# Alarm.net
KiCad netlist of a schematic drawn in EAGLE
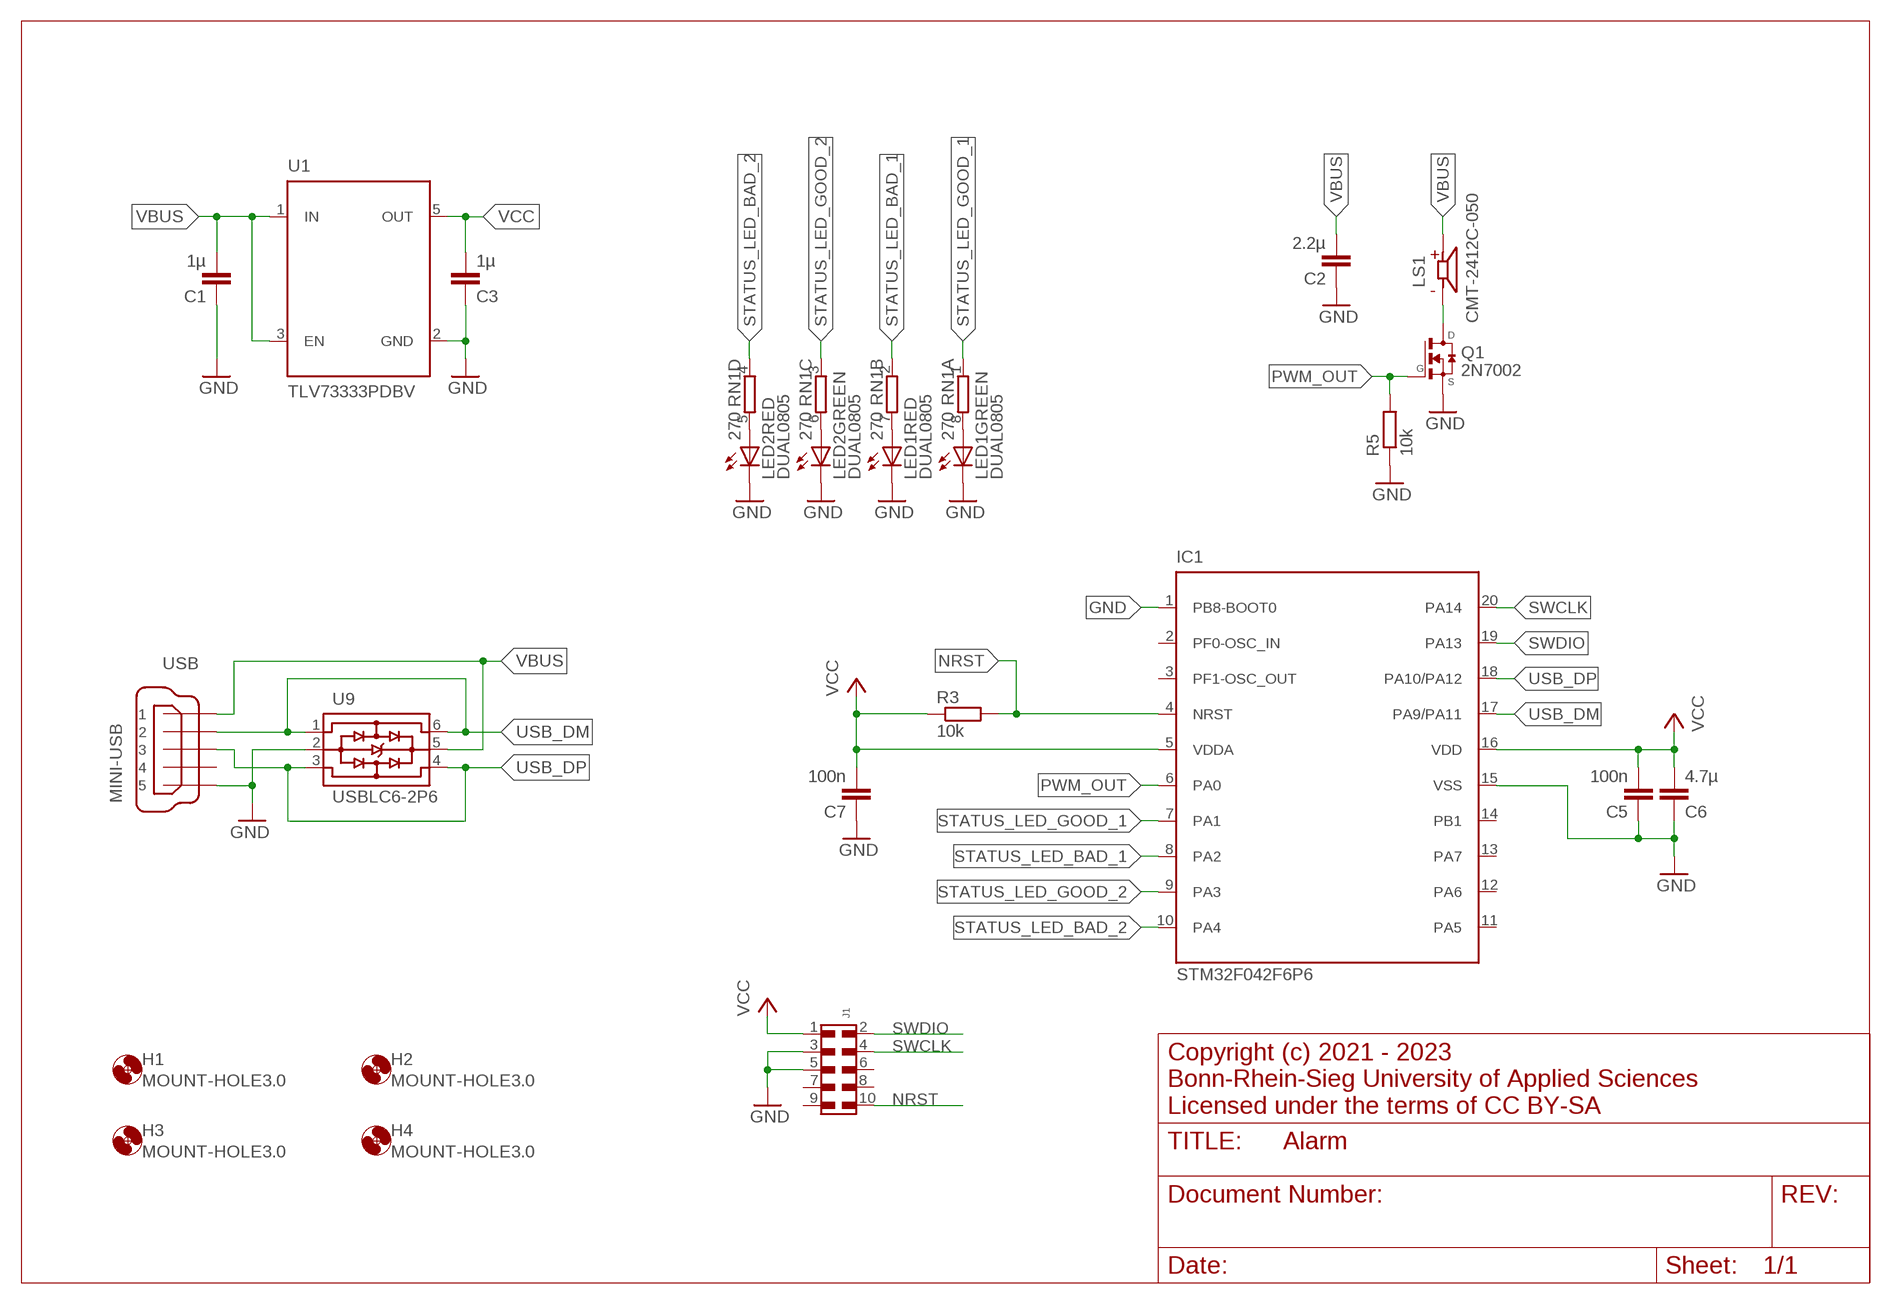
[diagram p0: schematic, sheet 1]

(export (version "E")
  (design (tool "Eeschema 10.0.6"))
  (components
    (comp (ref "C1")
      (value "1µ")
      (footprint "eagle-import:C0603")
      (libsource (lib "eagle-import") (part "C-EUC0603"))
    )
    (comp (ref "C2")
      (value "2.2µ")
      (footprint "eagle-import:C0603")
      (libsource (lib "eagle-import") (part "C-EUC0603"))
    )
    (comp (ref "C3")
      (value "1µ")
      (footprint "eagle-import:C0603")
      (libsource (lib "eagle-import") (part "C-EUC0603"))
    )
    (comp (ref "C5")
      (value "100n")
      (footprint "eagle-import:C0603")
      (libsource (lib "eagle-import") (part "C-EUC0603"))
    )
    (comp (ref "C6")
      (value "4.7µ")
      (footprint "eagle-import:C0603")
      (libsource (lib "eagle-import") (part "C-EUC0603"))
    )
    (comp (ref "C7")
      (value "100n")
      (footprint "eagle-import:C0603")
      (libsource (lib "eagle-import") (part "C-EUC0603"))
    )
    (comp (ref "H1")
      (value "MOUNT-HOLE3.0")
      (footprint "eagle-import:3,0")
      (libsource (lib "eagle-import") (part "MOUNT-HOLE3.0"))
    )
    (comp (ref "H2")
      (value "MOUNT-HOLE3.0")
      (footprint "eagle-import:3,0")
      (libsource (lib "eagle-import") (part "MOUNT-HOLE3.0"))
    )
    (comp (ref "H3")
      (value "MOUNT-HOLE3.0")
      (footprint "eagle-import:3,0")
      (libsource (lib "eagle-import") (part "MOUNT-HOLE3.0"))
    )
    (comp (ref "H4")
      (value "MOUNT-HOLE3.0")
      (footprint "eagle-import:3,0")
      (libsource (lib "eagle-import") (part "MOUNT-HOLE3.0"))
    )
    (comp (ref "IC1")
      (value "STM32F042F6P6")
      (footprint "eagle-import:TSSOP20")
      (libsource (lib "eagle-import") (part "STM32F042F?P66"))
    )
    (comp (ref "J1")
      (value "6210XX21021_62101021021")
      (footprint "eagle-import:62101021021")
      (libsource (lib "eagle-import") (part "6210XX21021_62101021021"))
    )
    (comp (ref "LED1")
      (value "DUAL0805")
      (footprint "eagle-import:CHIPLEDX2")
      (libsource (lib "eagle-import") (part "DUAL0805"))
    )
    (comp (ref "LED2")
      (value "DUAL0805")
      (footprint "eagle-import:CHIPLEDX2")
      (libsource (lib "eagle-import") (part "DUAL0805"))
    )
    (comp (ref "LS1")
      (value "CMT-2412C-050")
      (footprint "eagle-import:CUI_CMT-2412C-050")
      (fields (field (name "DIGI-KEY_PART_NUMBER") "102-3765-ND") (field (name "MF") "CUI"))
      (libsource (lib "eagle-import") (part "CMT-2412C-050"))
    )
    (comp (ref "Q1")
      (value "2N7002")
      (footprint "eagle-import:SOT23")
      (libsource (lib "eagle-import") (part "2N7002"))
    )
    (comp (ref "R3")
      (value "10k")
      (footprint "eagle-import:R0603")
      (libsource (lib "eagle-import") (part "R-EU_R0603"))
    )
    (comp (ref "R5")
      (value "10k")
      (footprint "eagle-import:R0603")
      (libsource (lib "eagle-import") (part "R-EU_R0603"))
    )
    (comp (ref "RN1")
      (value "270")
      (footprint "eagle-import:EXB38V")
      (libsource (lib "eagle-import") (part "4R-NEXB38V"))
    )
    (comp (ref "U1")
      (value "TLV73333PDBV")
      (footprint "eagle-import:SOT-23")
      (libsource (lib "eagle-import") (part "TLV733P?DBV33"))
    )
    (comp (ref "U9")
      (value "USBLC6-2P6")
      (footprint "eagle-import:SOT-666")
      (libsource (lib "eagle-import") (part "USBLC6-2P6"))
    )
    (comp (ref "USB")
      (value "MINI-USB")
      (footprint "eagle-import:32005-201")
      (libsource (lib "eagle-import") (part "MINI-USB-32005-201"))
    )
  )
  (nets
    (net (code "1") (name "GND") (class "Default")
      (node (ref "C1") (pin "1") (pinfunction "1_1") (pintype "passive"))
      (node (ref "C2") (pin "1") (pinfunction "1_1") (pintype "passive"))
      (node (ref "C3") (pin "1") (pinfunction "1_1") (pintype "passive"))
      (node (ref "C5") (pin "1") (pinfunction "1_1") (pintype "passive"))
      (node (ref "C6") (pin "1") (pinfunction "1_1") (pintype "passive"))
      (node (ref "C7") (pin "1") (pinfunction "1_1") (pintype "passive"))
      (node (ref "IC1") (pin "1") (pinfunction "PB8-BOOT0_1") (pintype "bidirectional"))
      (node (ref "IC1") (pin "15") (pinfunction "VSS_15") (pintype "bidirectional"))
      (node (ref "J1") (pin "3") (pinfunction "3_3") (pintype "passive"))
      (node (ref "J1") (pin "5") (pinfunction "5_5") (pintype "passive"))
      (node (ref "LED1") (pin "C1") (pinfunction "C_C1") (pintype "passive"))
      (node (ref "LED1") (pin "C2") (pinfunction "C_C2") (pintype "passive"))
      (node (ref "LED2") (pin "C1") (pinfunction "C_C1") (pintype "passive"))
      (node (ref "LED2") (pin "C2") (pinfunction "C_C2") (pintype "passive"))
      (node (ref "Q1") (pin "2") (pinfunction "S_2") (pintype "passive"))
      (node (ref "R5") (pin "1") (pinfunction "1_1") (pintype "passive"))
      (node (ref "U1") (pin "2") (pinfunction "GND_2") (pintype "bidirectional"))
      (node (ref "U9") (pin "2") (pinfunction "2_2") (pintype "passive"))
      (node (ref "USB") (pin "5") (pinfunction "5_5") (pintype "passive"))
    )
    (net (code "2") (name "NRST") (class "Default")
      (node (ref "IC1") (pin "4") (pinfunction "NRST_4") (pintype "bidirectional"))
      (node (ref "J1") (pin "10") (pinfunction "10_10") (pintype "passive"))
      (node (ref "R3") (pin "2") (pinfunction "2_2") (pintype "passive"))
    )
    (net (code "3") (name "Net-(LED1A-A)") (class "Default")
      (node (ref "LED1") (pin "A2") (pinfunction "A_A2") (pintype "passive"))
      (node (ref "RN1") (pin "8") (pinfunction "2_8") (pintype "passive"))
    )
    (net (code "4") (name "Net-(LED1B-A)") (class "Default")
      (node (ref "LED1") (pin "A1") (pinfunction "A_A1") (pintype "passive"))
      (node (ref "RN1") (pin "7") (pinfunction "2_7") (pintype "passive"))
    )
    (net (code "5") (name "Net-(LED2A-A)") (class "Default")
      (node (ref "LED2") (pin "A2") (pinfunction "A_A2") (pintype "passive"))
      (node (ref "RN1") (pin "6") (pinfunction "2_6") (pintype "passive"))
    )
    (net (code "6") (name "Net-(LED2B-A)") (class "Default")
      (node (ref "LED2") (pin "A1") (pinfunction "A_A1") (pintype "passive"))
      (node (ref "RN1") (pin "5") (pinfunction "2_5") (pintype "passive"))
    )
    (net (code "7") (name "Net-(Q1-D)") (class "Default")
      (node (ref "LS1") (pin "N") (pinfunction "N_N") (pintype "passive"))
      (node (ref "Q1") (pin "3") (pinfunction "D_3") (pintype "passive"))
    )
    (net (code "8") (name "PWM_OUT") (class "Default")
      (node (ref "IC1") (pin "6") (pinfunction "PA0_6") (pintype "bidirectional"))
      (node (ref "Q1") (pin "1") (pinfunction "G_1") (pintype "passive"))
      (node (ref "R5") (pin "2") (pinfunction "2_2") (pintype "passive"))
    )
    (net (code "9") (name "STATUS_LED_BAD_1") (class "Default")
      (node (ref "IC1") (pin "8") (pinfunction "PA2_8") (pintype "bidirectional"))
      (node (ref "RN1") (pin "2") (pinfunction "1_2") (pintype "passive"))
    )
    (net (code "10") (name "STATUS_LED_BAD_2") (class "Default")
      (node (ref "IC1") (pin "10") (pinfunction "PA4_10") (pintype "bidirectional"))
      (node (ref "RN1") (pin "4") (pinfunction "1_4") (pintype "passive"))
    )
    (net (code "11") (name "STATUS_LED_GOOD_1") (class "Default")
      (node (ref "IC1") (pin "7") (pinfunction "PA1_7") (pintype "bidirectional"))
      (node (ref "RN1") (pin "1") (pinfunction "1_1") (pintype "passive"))
    )
    (net (code "12") (name "STATUS_LED_GOOD_2") (class "Default")
      (node (ref "IC1") (pin "9") (pinfunction "PA3_9") (pintype "bidirectional"))
      (node (ref "RN1") (pin "3") (pinfunction "1_3") (pintype "passive"))
    )
    (net (code "13") (name "SWCLK") (class "Default")
      (node (ref "IC1") (pin "20") (pinfunction "PA14_20") (pintype "bidirectional"))
      (node (ref "J1") (pin "4") (pinfunction "4_4") (pintype "passive"))
    )
    (net (code "14") (name "SWDIO") (class "Default")
      (node (ref "IC1") (pin "19") (pinfunction "PA13_19") (pintype "bidirectional"))
      (node (ref "J1") (pin "2") (pinfunction "2_2") (pintype "passive"))
    )
    (net (code "15") (name "USB_DM") (class "Default")
      (node (ref "IC1") (pin "17") (pinfunction "PA9/PA11_17") (pintype "bidirectional"))
      (node (ref "U9") (pin "1") (pinfunction "1_1") (pintype "bidirectional"))
      (node (ref "U9") (pin "6") (pinfunction "6_6") (pintype "bidirectional"))
      (node (ref "USB") (pin "2") (pinfunction "2_2") (pintype "passive"))
    )
    (net (code "16") (name "USB_DP") (class "Default")
      (node (ref "IC1") (pin "18") (pinfunction "PA10/PA12_18") (pintype "bidirectional"))
      (node (ref "U9") (pin "3") (pinfunction "3_3") (pintype "bidirectional"))
      (node (ref "U9") (pin "4") (pinfunction "4_4") (pintype "bidirectional"))
      (node (ref "USB") (pin "3") (pinfunction "3_3") (pintype "passive"))
    )
    (net (code "17") (name "VBUS") (class "Default")
      (node (ref "C1") (pin "2") (pinfunction "2_2") (pintype "passive"))
      (node (ref "C2") (pin "2") (pinfunction "2_2") (pintype "passive"))
      (node (ref "LS1") (pin "P") (pinfunction "P_P") (pintype "passive"))
      (node (ref "U1") (pin "1") (pinfunction "IN_1") (pintype "bidirectional"))
      (node (ref "U1") (pin "3") (pinfunction "EN_3") (pintype "bidirectional"))
      (node (ref "U9") (pin "5") (pinfunction "5_5") (pintype "passive"))
      (node (ref "USB") (pin "1") (pinfunction "1_1") (pintype "passive"))
    )
    (net (code "18") (name "VCC") (class "Default")
      (node (ref "C3") (pin "2") (pinfunction "2_2") (pintype "passive"))
      (node (ref "C5") (pin "2") (pinfunction "2_2") (pintype "passive"))
      (node (ref "C6") (pin "2") (pinfunction "2_2") (pintype "passive"))
      (node (ref "C7") (pin "2") (pinfunction "2_2") (pintype "passive"))
      (node (ref "IC1") (pin "16") (pinfunction "VDD_16") (pintype "bidirectional"))
      (node (ref "IC1") (pin "5") (pinfunction "VDDA_5") (pintype "bidirectional"))
      (node (ref "J1") (pin "1") (pinfunction "1_1") (pintype "passive"))
      (node (ref "R3") (pin "1") (pinfunction "1_1") (pintype "passive"))
      (node (ref "U1") (pin "5") (pinfunction "OUT_5") (pintype "bidirectional"))
    )
    (net (code "19") (name "unconnected-(IC1-PA5-Pad11)") (class "Default")
      (node (ref "IC1") (pin "11") (pinfunction "PA5_11") (pintype "bidirectional"))
    )
    (net (code "20") (name "unconnected-(IC1-PA6-Pad12)") (class "Default")
      (node (ref "IC1") (pin "12") (pinfunction "PA6_12") (pintype "bidirectional"))
    )
    (net (code "21") (name "unconnected-(IC1-PA7-Pad13)") (class "Default")
      (node (ref "IC1") (pin "13") (pinfunction "PA7_13") (pintype "bidirectional"))
    )
    (net (code "22") (name "unconnected-(IC1-PB1-Pad14)") (class "Default")
      (node (ref "IC1") (pin "14") (pinfunction "PB1_14") (pintype "bidirectional"))
    )
    (net (code "23") (name "unconnected-(IC1-PF0-OSC_IN-Pad2)") (class "Default")
      (node (ref "IC1") (pin "2") (pinfunction "PF0-OSC_IN_2") (pintype "bidirectional"))
    )
    (net (code "24") (name "unconnected-(IC1-PF1-OSC_OUT-Pad3)") (class "Default")
      (node (ref "IC1") (pin "3") (pinfunction "PF1-OSC_OUT_3") (pintype "bidirectional"))
    )
    (net (code "25") (name "unconnected-(J1-Pad6)") (class "Default")
      (node (ref "J1") (pin "6") (pinfunction "6_6") (pintype "passive"))
    )
    (net (code "26") (name "unconnected-(J1-Pad7)") (class "Default")
      (node (ref "J1") (pin "7") (pinfunction "7_7") (pintype "passive"))
    )
    (net (code "27") (name "unconnected-(J1-Pad8)") (class "Default")
      (node (ref "J1") (pin "8") (pinfunction "8_8") (pintype "passive"))
    )
    (net (code "28") (name "unconnected-(J1-Pad9)") (class "Default")
      (node (ref "J1") (pin "9") (pinfunction "9_9") (pintype "passive"))
    )
    (net (code "29") (name "unconnected-(USB-Pad4)") (class "Default")
      (node (ref "USB") (pin "4") (pinfunction "4_4") (pintype "passive"))
    )
  )
)
